# SCH_hackercard_2024-07-13.net
KiCad netlist of a schematic drawn in EasyEDA
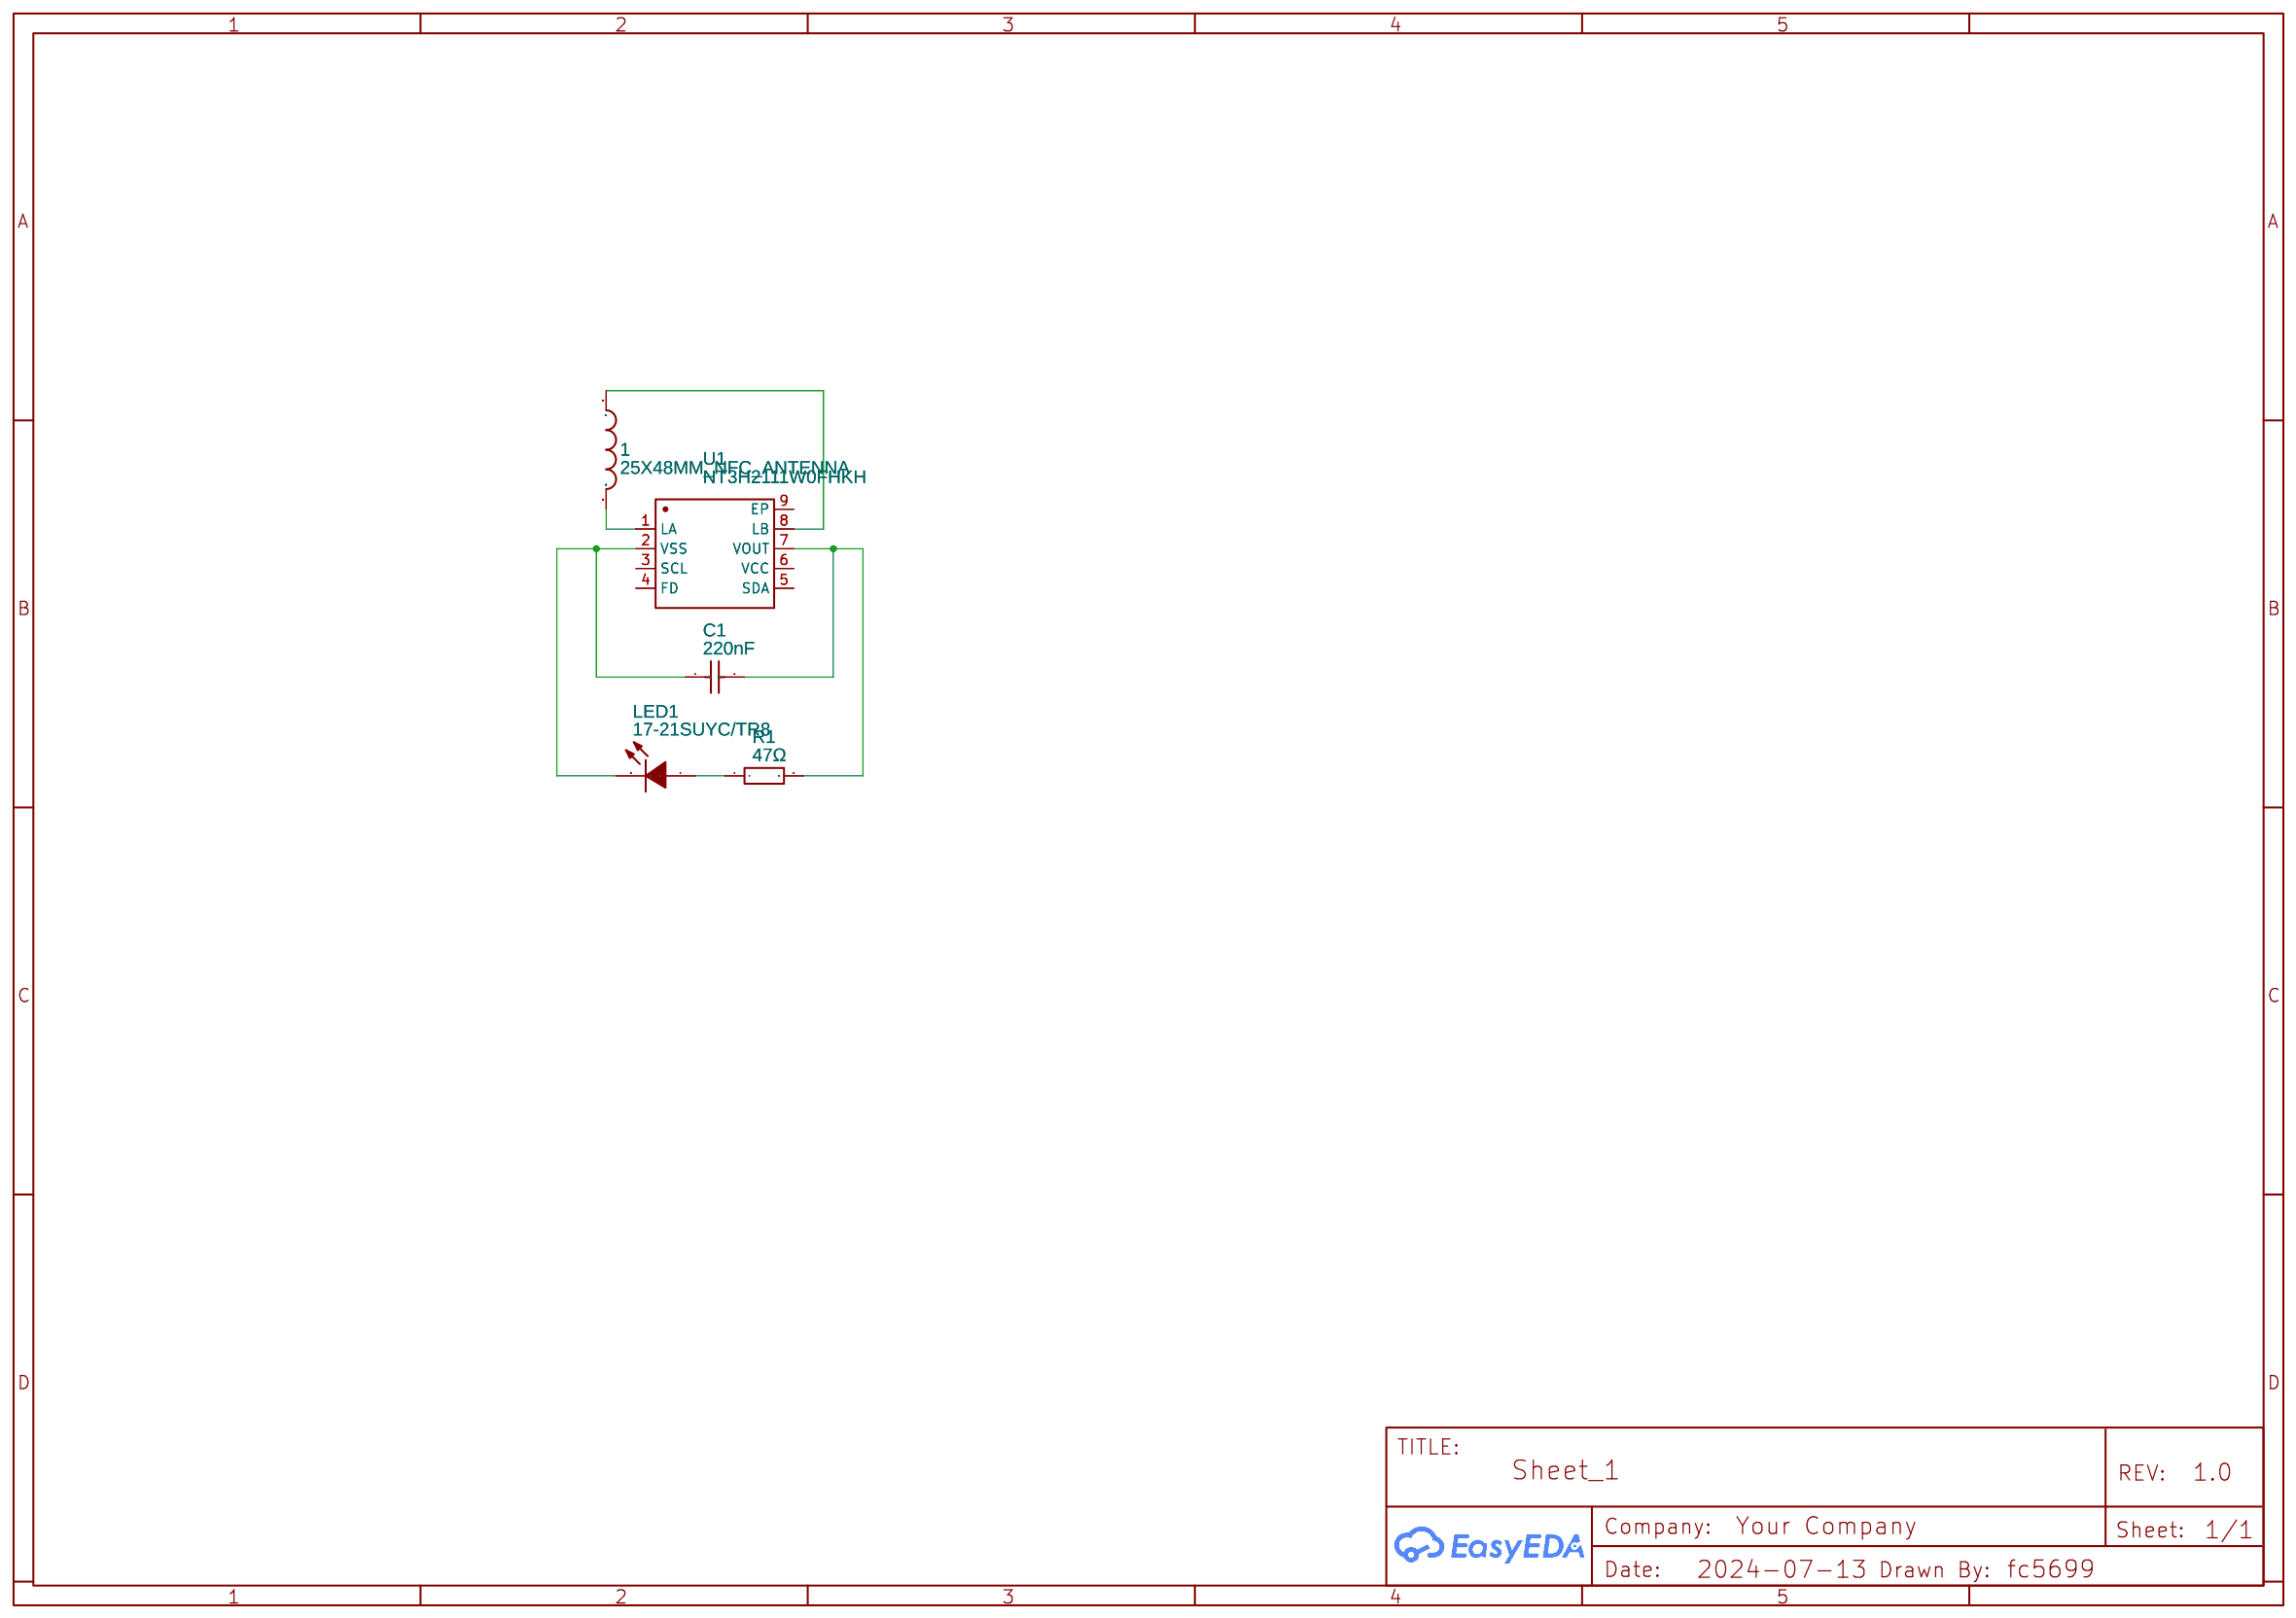
[diagram p0: schematic sheet]

(export (version "E")
  (design (tool "Eeschema 10.0.6"))
  (components
    (comp (ref "1") (value "25X48MM_NFC_ANTENNA") (libsource (lib "") (part "25X48MM_NFC_ANTENNA")))
    (comp (ref "C1")
      (value "220nF")
      (fields
        (field (name "Manufacturer Part") "CL10B224KA8NNNC")
        (field (name "Manufacturer") "SAMSUNG(三星)")
      )
      (libsource (lib "") (part "CL10B224KA8NNNC"))
    )
    (comp (ref "LED1")
      (value "17-21SUYC/TR8")
      (fields (field (name "Manufacturer Part") "KT-0805黄灯") (field (name "Manufacturer") "KENTO"))
      (libsource (lib "") (part "17-21SUYC/TR8"))
    )
    (comp (ref "R1")
      (value "47Ω")
      (fields
        (field (name "Manufacturer Part") "0603WAF470JT5E")
        (field (name "Manufacturer") "UNI-ROYAL(厚声)")
      )
      (libsource (lib "") (part "0603WAF470JT5E"))
    )
    (comp (ref "U1")
      (value "NT3H2111W0FHKH")
      (fields (field (name "Manufacturer") "NXP(恩智浦)"))
      (libsource (lib "") (part "NT3H2111W0FHKH"))
    )
  )
  (nets
    (net (code "1") (name "Net-(LED1-+)") (class "Default")
      (node (ref "LED1") (pin "1") (pinfunction "+_1") (pintype "unspecified"))
      (node (ref "R1") (pin "1") (pinfunction "1_1") (pintype "input"))
    )
    (net (code "2") (name "Net-(LED1--)") (class "Default")
      (node (ref "C1") (pin "1") (pinfunction "1_1") (pintype "input"))
      (node (ref "LED1") (pin "2") (pinfunction "-_2") (pintype "unspecified"))
      (node (ref "U1") (pin "2") (pinfunction "VSS_2") (pintype "unspecified"))
    )
    (net (code "3") (name "Net-(U1-LA)") (class "Default")
      (node (ref "1") (pin "P$2") (pinfunction "P$2_P$2") (pintype "bidirectional"))
      (node (ref "U1") (pin "1") (pinfunction "LA_1") (pintype "unspecified"))
    )
    (net (code "4") (name "Net-(U1-LB)") (class "Default")
      (node (ref "1") (pin "P$1") (pinfunction "P$1_P$1") (pintype "bidirectional"))
      (node (ref "U1") (pin "8") (pinfunction "LB_8") (pintype "unspecified"))
    )
    (net (code "5") (name "Net-(U1-VOUT)") (class "Default")
      (node (ref "C1") (pin "2") (pinfunction "2_2") (pintype "input"))
      (node (ref "R1") (pin "2") (pinfunction "2_2") (pintype "input"))
      (node (ref "U1") (pin "7") (pinfunction "VOUT_7") (pintype "unspecified"))
    )
    (net (code "6") (name "unconnected-(U1-EP-Pad9)") (class "Default")
      (node (ref "U1") (pin "9") (pinfunction "EP_9") (pintype "unspecified"))
    )
    (net (code "7") (name "unconnected-(U1-FD-Pad4)") (class "Default")
      (node (ref "U1") (pin "4") (pinfunction "FD_4") (pintype "unspecified"))
    )
    (net (code "8") (name "unconnected-(U1-SCL-Pad3)") (class "Default")
      (node (ref "U1") (pin "3") (pinfunction "SCL_3") (pintype "unspecified"))
    )
    (net (code "9") (name "unconnected-(U1-SDA-Pad5)") (class "Default")
      (node (ref "U1") (pin "5") (pinfunction "SDA_5") (pintype "unspecified"))
    )
    (net (code "10") (name "unconnected-(U1-VCC-Pad6)") (class "Default")
      (node (ref "U1") (pin "6") (pinfunction "VCC_6") (pintype "unspecified"))
    )
  )
)
